# Skematic_AT89C51.net
KiCad netlist of a schematic drawn in Altium Designer
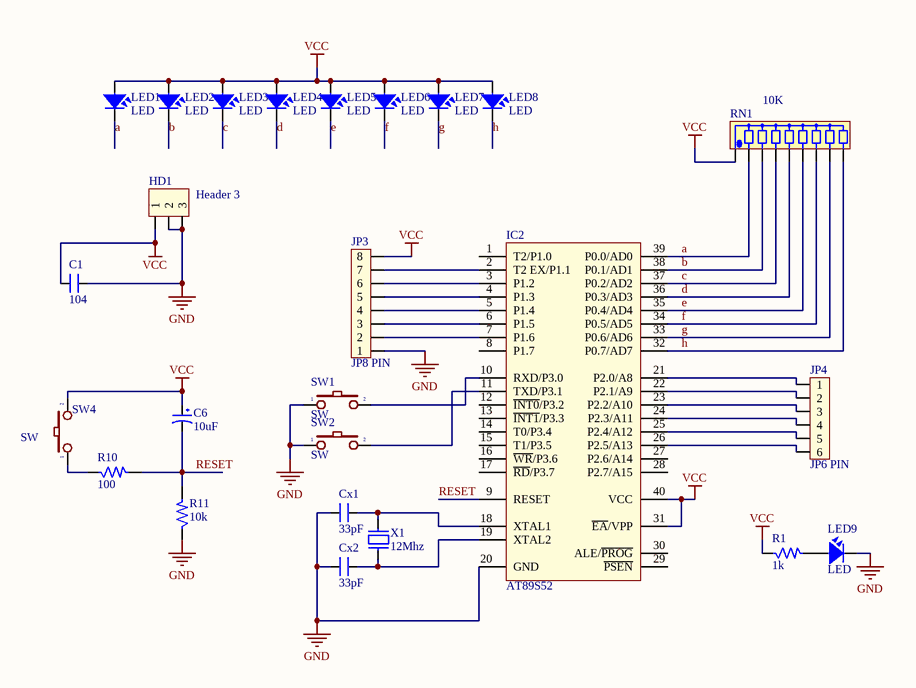
[diagram p0: Skematic AT89C51.SchDoc]

(export (version "E")
  (design (tool "Eeschema 10.0.6"))
  (components
    (comp (ref "C1")
      (value "104")
      (footprint "CN2")
      (description "Cap np 104 => 105pF")
      (libsource (lib "syhaunguyen") (part "CN2"))
    )
    (comp (ref "C6")
      (value "10uF")
      (footprint "CP1/2")
      (description "Cap P  0,1uF < 22uF , 16 - 50V")
      (libsource (lib "syhaunguyen") (part "CP1"))
    )
    (comp (ref "Cx1")
      (value "33pF")
      (footprint "CN1")
      (description "Cremic For Xtal 1pF => 100pF")
      (libsource (lib "syhaunguyen") (part "CN0"))
    )
    (comp (ref "Cx2")
      (value "33pF")
      (footprint "CN1")
      (description "Cremic For Xtal 1pF => 100pF")
      (libsource (lib "syhaunguyen") (part "CN0"))
    )
    (comp (ref "HD1")
      (value "Header 3")
      (footprint "HED3T")
      (description "Header 3 (Green)")
      (libsource (lib "syhaunguyen") (part "Hed3"))
    )
    (comp (ref "IC2")
      (value "AT89S52")
      (footprint "DIP40/W0.6")
      (description "Atmel AT89C52, 8k Byte Flash Memory , 40 Pin")
      (libsource (lib "syhaunguyen") (part "AT89C52"))
    )
    (comp (ref "JP3") (value "JP8 PIN") (footprint "JP8") (libsource (lib "syhaunguyen") (part "JP8")))
    (comp (ref "JP4") (value "JP6 PIN") (footprint "JP6") (libsource (lib "syhaunguyen") (part "JP6")))
    (comp (ref "LED1")
      (value "LED")
      (footprint "LED-3")
      (description "LED Single colour Green and Red")
      (libsource (lib "syhaunguyen") (part "LED"))
    )
    (comp (ref "LED2")
      (value "LED")
      (footprint "LED-3")
      (description "LED Single colour Green and Red")
      (libsource (lib "syhaunguyen") (part "LED"))
    )
    (comp (ref "LED3")
      (value "LED")
      (footprint "LED-3")
      (description "LED Single colour Green and Red")
      (libsource (lib "syhaunguyen") (part "LED"))
    )
    (comp (ref "LED4")
      (value "LED")
      (footprint "LED-3")
      (description "LED Single colour Green and Red")
      (libsource (lib "syhaunguyen") (part "LED"))
    )
    (comp (ref "LED5")
      (value "LED")
      (footprint "LED-3")
      (description "LED Single colour Green and Red")
      (libsource (lib "syhaunguyen") (part "LED"))
    )
    (comp (ref "LED6")
      (value "LED")
      (footprint "LED-3")
      (description "LED Single colour Green and Red")
      (libsource (lib "syhaunguyen") (part "LED"))
    )
    (comp (ref "LED7")
      (value "LED")
      (footprint "LED-3")
      (description "LED Single colour Green and Red")
      (libsource (lib "syhaunguyen") (part "LED"))
    )
    (comp (ref "LED8")
      (value "LED")
      (footprint "LED-3")
      (description "LED Single colour Green and Red")
      (libsource (lib "syhaunguyen") (part "LED"))
    )
    (comp (ref "LED9")
      (value "LED")
      (footprint "LED-3")
      (description "LED Single colour Green and Red")
      (libsource (lib "syhaunguyen") (part "LED"))
    )
    (comp (ref "R1")
      (value "1k")
      (footprint "R1/4W")
      (description "Resistor 1/4W")
      (libsource (lib "syhaunguyen") (part "R"))
    )
    (comp (ref "R10")
      (value "100")
      (footprint "R1/4W")
      (description "Resistor 1/4W")
      (libsource (lib "syhaunguyen") (part "R"))
    )
    (comp (ref "R11")
      (value "10k")
      (footprint "R1/4W")
      (description "Resistor 1/4W")
      (libsource (lib "syhaunguyen") (part "R"))
    )
    (comp (ref "RN1")
      (value "10K")
      (footprint "RN8")
      (description "Resistor 8 (Thanh)")
      (libsource (lib "syhaunguyen") (part "RN8"))
    )
    (comp (ref "SW1")
      (value "SW")
      (footprint "SW2")
      (description "Switch button 2 pin")
      (libsource (lib "syhaunguyen") (part "SW2"))
    )
    (comp (ref "SW2")
      (value "SW")
      (footprint "SW2")
      (description "Switch button 2 pin")
      (libsource (lib "syhaunguyen") (part "SW2"))
    )
    (comp (ref "SW4")
      (value "SW")
      (footprint "SW2")
      (description "Switch button 2 pin")
      (libsource (lib "syhaunguyen") (part "SW2"))
    )
    (comp (ref "X1")
      (value "12Mhz")
      (footprint "XT2")
      (description "Crystal For all Crystal 2pin.")
      (libsource (lib "syhaunguyen") (part "XT2"))
    )
  )
  (nets
    (net (code "1") (name "/RESET") (class "Default")
      (node (ref "C6") (pin "2") (pinfunction "2_2") (pintype "passive"))
      (node (ref "IC2") (pin "9") (pinfunction "RESET_9") (pintype "passive"))
      (node (ref "R10") (pin "2") (pinfunction "2_2") (pintype "passive"))
      (node (ref "R11") (pin "2") (pinfunction "2_2") (pintype "passive"))
    )
    (net (code "2") (name "/a") (class "Default")
      (node (ref "IC2") (pin "39") (pinfunction "P0.0/AD0_39") (pintype "passive"))
      (node (ref "LED1") (pin "2") (pinfunction "2_2") (pintype "passive"))
      (node (ref "RN1") (pin "2") (pinfunction "2_2") (pintype "passive"))
    )
    (net (code "3") (name "/b") (class "Default")
      (node (ref "IC2") (pin "38") (pinfunction "P0.1/AD1_38") (pintype "passive"))
      (node (ref "LED2") (pin "2") (pinfunction "2_2") (pintype "passive"))
      (node (ref "RN1") (pin "3") (pinfunction "3_3") (pintype "passive"))
    )
    (net (code "4") (name "/c") (class "Default")
      (node (ref "IC2") (pin "37") (pinfunction "P0.2/AD2_37") (pintype "passive"))
      (node (ref "LED3") (pin "2") (pinfunction "2_2") (pintype "passive"))
      (node (ref "RN1") (pin "4") (pinfunction "4_4") (pintype "passive"))
    )
    (net (code "5") (name "/d") (class "Default")
      (node (ref "IC2") (pin "36") (pinfunction "P0.3/AD3_36") (pintype "passive"))
      (node (ref "LED4") (pin "2") (pinfunction "2_2") (pintype "passive"))
      (node (ref "RN1") (pin "5") (pinfunction "5_5") (pintype "passive"))
    )
    (net (code "6") (name "/e") (class "Default")
      (node (ref "IC2") (pin "35") (pinfunction "P0.4/AD4_35") (pintype "passive"))
      (node (ref "LED5") (pin "2") (pinfunction "2_2") (pintype "passive"))
      (node (ref "RN1") (pin "6") (pinfunction "6_6") (pintype "passive"))
    )
    (net (code "7") (name "/f") (class "Default")
      (node (ref "IC2") (pin "34") (pinfunction "P0.5/AD5_34") (pintype "passive"))
      (node (ref "LED6") (pin "2") (pinfunction "2_2") (pintype "passive"))
      (node (ref "RN1") (pin "7") (pinfunction "7_7") (pintype "passive"))
    )
    (net (code "8") (name "/g") (class "Default")
      (node (ref "IC2") (pin "33") (pinfunction "P0.6/AD6_33") (pintype "passive"))
      (node (ref "LED7") (pin "2") (pinfunction "2_2") (pintype "passive"))
      (node (ref "RN1") (pin "8") (pinfunction "8_8") (pintype "passive"))
    )
    (net (code "9") (name "/h") (class "Default")
      (node (ref "IC2") (pin "32") (pinfunction "P0.7/AD7_32") (pintype "passive"))
      (node (ref "LED8") (pin "2") (pinfunction "2_2") (pintype "passive"))
      (node (ref "RN1") (pin "9") (pinfunction "9_9") (pintype "passive"))
    )
    (net (code "10") (name "GND") (class "Default")
      (node (ref "C1") (pin "2") (pinfunction "2_2") (pintype "passive"))
      (node (ref "Cx1") (pin "2") (pinfunction "2_2") (pintype "passive"))
      (node (ref "Cx2") (pin "1") (pinfunction "1_1") (pintype "passive"))
      (node (ref "HD1") (pin "2") (pinfunction "2_2") (pintype "passive"))
      (node (ref "HD1") (pin "3") (pinfunction "3_3") (pintype "passive"))
      (node (ref "IC2") (pin "20") (pinfunction "GND_20") (pintype "open_emitter"))
      (node (ref "JP3") (pin "1") (pinfunction "1_1") (pintype "passive"))
      (node (ref "LED9") (pin "2") (pinfunction "2_2") (pintype "passive"))
      (node (ref "R11") (pin "1") (pinfunction "1_1") (pintype "passive"))
      (node (ref "SW1") (pin "1") (pinfunction "1_1") (pintype "passive"))
      (node (ref "SW2") (pin "1") (pinfunction "1_1") (pintype "passive"))
    )
    (net (code "11") (name "Net-(IC2-P1.2)") (class "Default")
      (node (ref "IC2") (pin "3") (pinfunction "P1.2_3") (pintype "passive"))
      (node (ref "JP3") (pin "6") (pinfunction "6_6") (pintype "passive"))
    )
    (net (code "12") (name "Net-(IC2-P1.3)") (class "Default")
      (node (ref "IC2") (pin "4") (pinfunction "P1.3_4") (pintype "passive"))
      (node (ref "JP3") (pin "5") (pinfunction "5_5") (pintype "passive"))
    )
    (net (code "13") (name "Net-(IC2-P1.4)") (class "Default")
      (node (ref "IC2") (pin "5") (pinfunction "P1.4_5") (pintype "passive"))
      (node (ref "JP3") (pin "4") (pinfunction "4_4") (pintype "passive"))
    )
    (net (code "14") (name "Net-(IC2-P1.5)") (class "Default")
      (node (ref "IC2") (pin "6") (pinfunction "P1.5_6") (pintype "passive"))
      (node (ref "JP3") (pin "3") (pinfunction "3_3") (pintype "passive"))
    )
    (net (code "15") (name "Net-(IC2-P1.6)") (class "Default")
      (node (ref "IC2") (pin "7") (pinfunction "P1.6_7") (pintype "passive"))
      (node (ref "JP3") (pin "2") (pinfunction "2_2") (pintype "passive"))
    )
    (net (code "16") (name "Net-(IC2-P2.0{slash}A8)") (class "Default")
      (node (ref "IC2") (pin "21") (pinfunction "P2.0/A8_21") (pintype "passive"))
      (node (ref "JP4") (pin "1") (pinfunction "1_1") (pintype "passive"))
    )
    (net (code "17") (name "Net-(IC2-P2.1{slash}A9)") (class "Default")
      (node (ref "IC2") (pin "22") (pinfunction "P2.1/A9_22") (pintype "passive"))
      (node (ref "JP4") (pin "2") (pinfunction "2_2") (pintype "passive"))
    )
    (net (code "18") (name "Net-(IC2-P2.2{slash}A10)") (class "Default")
      (node (ref "IC2") (pin "23") (pinfunction "P2.2/A10_23") (pintype "passive"))
      (node (ref "JP4") (pin "3") (pinfunction "3_3") (pintype "passive"))
    )
    (net (code "19") (name "Net-(IC2-P2.3{slash}A11)") (class "Default")
      (node (ref "IC2") (pin "24") (pinfunction "P2.3/A11_24") (pintype "passive"))
      (node (ref "JP4") (pin "4") (pinfunction "4_4") (pintype "passive"))
    )
    (net (code "20") (name "Net-(IC2-P2.4{slash}A12)") (class "Default")
      (node (ref "IC2") (pin "25") (pinfunction "P2.4/A12_25") (pintype "passive"))
      (node (ref "JP4") (pin "5") (pinfunction "5_5") (pintype "passive"))
    )
    (net (code "21") (name "Net-(IC2-P2.5{slash}A13)") (class "Default")
      (node (ref "IC2") (pin "26") (pinfunction "P2.5/A13_26") (pintype "passive"))
      (node (ref "JP4") (pin "6") (pinfunction "6_6") (pintype "passive"))
    )
    (net (code "22") (name "Net-(IC2-RXD{slash}P3.0)") (class "Default")
      (node (ref "IC2") (pin "10") (pinfunction "RXD/P3.0_10") (pintype "passive"))
      (node (ref "SW1") (pin "2") (pinfunction "2_2") (pintype "passive"))
    )
    (net (code "23") (name "Net-(IC2-T2_EX{slash}P1.1)") (class "Default")
      (node (ref "IC2") (pin "2") (pinfunction "T2_EX/P1.1_2") (pintype "passive"))
      (node (ref "JP3") (pin "7") (pinfunction "7_7") (pintype "passive"))
    )
    (net (code "24") (name "Net-(IC2-TXD{slash}P3.1)") (class "Default")
      (node (ref "IC2") (pin "11") (pinfunction "TXD/P3.1_11") (pintype "passive"))
      (node (ref "SW2") (pin "2") (pinfunction "2_2") (pintype "passive"))
    )
    (net (code "25") (name "Net-(IC2-XTAL1)") (class "Default")
      (node (ref "Cx1") (pin "1") (pinfunction "1_1") (pintype "passive"))
      (node (ref "IC2") (pin "18") (pinfunction "XTAL1_18") (pintype "passive"))
      (node (ref "X1") (pin "2") (pinfunction "2_2") (pintype "passive"))
    )
    (net (code "26") (name "Net-(IC2-XTAL2)") (class "Default")
      (node (ref "Cx2") (pin "2") (pinfunction "2_2") (pintype "passive"))
      (node (ref "IC2") (pin "19") (pinfunction "XTAL2_19") (pintype "passive"))
      (node (ref "X1") (pin "1") (pinfunction "1_1") (pintype "passive"))
    )
    (net (code "27") (name "Net-(LED9-Pad1)") (class "Default")
      (node (ref "LED9") (pin "1") (pinfunction "1_1") (pintype "passive"))
      (node (ref "R1") (pin "2") (pinfunction "2_2") (pintype "passive"))
    )
    (net (code "28") (name "Net-(R10-Pad1)") (class "Default")
      (node (ref "R10") (pin "1") (pinfunction "1_1") (pintype "passive"))
      (node (ref "SW4") (pin "1") (pinfunction "1_1") (pintype "passive"))
    )
    (net (code "29") (name "VCC") (class "Default")
      (node (ref "C1") (pin "1") (pinfunction "1_1") (pintype "passive"))
      (node (ref "C6") (pin "1") (pinfunction "1_1") (pintype "passive"))
      (node (ref "HD1") (pin "1") (pinfunction "1_1") (pintype "passive"))
      (node (ref "IC2") (pin "31") (pinfunction "~{EA}/VPP_31") (pintype "passive"))
      (node (ref "IC2") (pin "40") (pinfunction "VCC_40") (pintype "power_in"))
      (node (ref "JP3") (pin "8") (pinfunction "8_8") (pintype "passive"))
      (node (ref "LED1") (pin "1") (pinfunction "1_1") (pintype "passive"))
      (node (ref "LED2") (pin "1") (pinfunction "1_1") (pintype "passive"))
      (node (ref "LED3") (pin "1") (pinfunction "1_1") (pintype "passive"))
      (node (ref "LED4") (pin "1") (pinfunction "1_1") (pintype "passive"))
      (node (ref "LED5") (pin "1") (pinfunction "1_1") (pintype "passive"))
      (node (ref "LED6") (pin "1") (pinfunction "1_1") (pintype "passive"))
      (node (ref "LED7") (pin "1") (pinfunction "1_1") (pintype "passive"))
      (node (ref "LED8") (pin "1") (pinfunction "1_1") (pintype "passive"))
      (node (ref "R1") (pin "1") (pinfunction "1_1") (pintype "passive"))
      (node (ref "RN1") (pin "1") (pinfunction "1_1") (pintype "passive"))
      (node (ref "SW4") (pin "2") (pinfunction "2_2") (pintype "passive"))
    )
    (net (code "30") (name "unconnected-(IC2-ALE{slash}~{PROG}-Pad30)") (class "Default")
      (node (ref "IC2") (pin "30") (pinfunction "ALE/~{PROG}_30") (pintype "passive"))
    )
    (net (code "31") (name "unconnected-(IC2-P1.7-Pad8)") (class "Default")
      (node (ref "IC2") (pin "8") (pinfunction "P1.7_8") (pintype "passive"))
    )
    (net (code "32") (name "unconnected-(IC2-P2.6{slash}A14-Pad27)") (class "Default")
      (node (ref "IC2") (pin "27") (pinfunction "P2.6/A14_27") (pintype "passive"))
    )
    (net (code "33") (name "unconnected-(IC2-P2.7{slash}A15-Pad28)") (class "Default")
      (node (ref "IC2") (pin "28") (pinfunction "P2.7/A15_28") (pintype "passive"))
    )
    (net (code "34") (name "unconnected-(IC2-T0{slash}P3.4-Pad14)") (class "Default")
      (node (ref "IC2") (pin "14") (pinfunction "T0/P3.4_14") (pintype "passive"))
    )
    (net (code "35") (name "unconnected-(IC2-T1{slash}P3.5-Pad15)") (class "Default")
      (node (ref "IC2") (pin "15") (pinfunction "T1/P3.5_15") (pintype "passive"))
    )
    (net (code "36") (name "unconnected-(IC2-T2{slash}P1.0-Pad1)") (class "Default")
      (node (ref "IC2") (pin "1") (pinfunction "T2/P1.0_1") (pintype "passive"))
    )
    (net (code "37") (name "unconnected-(IC2-~{INT0}{slash}P3.2-Pad12)") (class "Default")
      (node (ref "IC2") (pin "12") (pinfunction "~{INT0}/P3.2_12") (pintype "passive"))
    )
    (net (code "38") (name "unconnected-(IC2-~{INT1}{slash}P3.3-Pad13)") (class "Default")
      (node (ref "IC2") (pin "13") (pinfunction "~{INT1}/P3.3_13") (pintype "passive"))
    )
    (net (code "39") (name "unconnected-(IC2-~{PSEN}-Pad29)") (class "Default")
      (node (ref "IC2") (pin "29") (pinfunction "~{PSEN}_29") (pintype "passive"))
    )
    (net (code "40") (name "unconnected-(IC2-~{RD}{slash}P3.7-Pad17)") (class "Default")
      (node (ref "IC2") (pin "17") (pinfunction "~{RD}/P3.7_17") (pintype "passive"))
    )
    (net (code "41") (name "unconnected-(IC2-~{WR}{slash}P3.6-Pad16)") (class "Default")
      (node (ref "IC2") (pin "16") (pinfunction "~{WR}/P3.6_16") (pintype "passive"))
    )
  )
)
